# dep-switches.net
KiCad netlist of a schematic drawn in Altium Designer
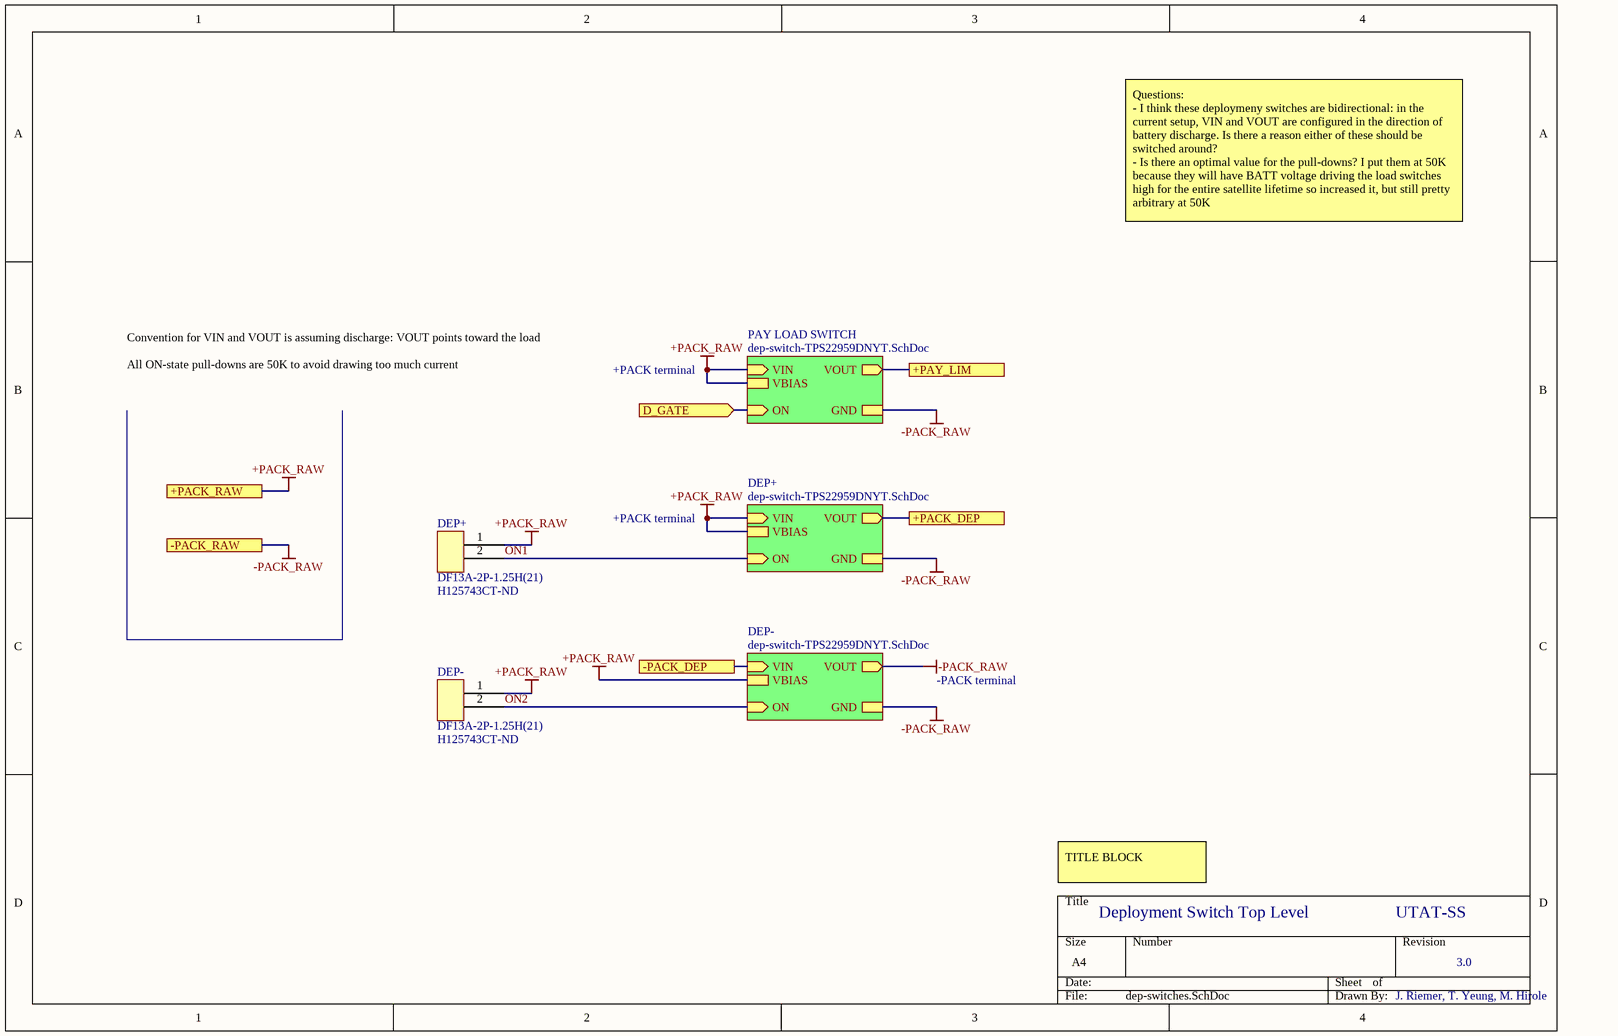
[diagram p0: dep-switches.SchDoc]

(export (version "E")
  (design (tool "Eeschema 10.0.6"))
  (components
    (comp (ref "DEP+")
      (value "DF13A-2P-1.25H(21)")
      (footprint "DF13A-2P-1.25H(21)")
      (description "2 pos DF13 right angle surface mount connector")
      (fields (field (name "SUPPLIER PART NUMBER 1") "H125743CT-ND"))
      (libsource (lib "heron-general") (part "DF13A-2P-1.25H(21)"))
    )
    (comp (ref "DEP-")
      (value "DF13A-2P-1.25H(21)")
      (footprint "DF13A-2P-1.25H(21)")
      (description "2 pos DF13 right angle surface mount connector")
      (fields (field (name "SUPPLIER PART NUMBER 1") "H125743CT-ND"))
      (libsource (lib "heron-general") (part "DF13A-2P-1.25H(21)"))
    )
  )
  (nets
    (net (code "1") (name "+PACK_RAW") (class "Default")
      (node (ref "DEP+") (pin "1") (pintype "passive"))
      (node (ref "DEP-") (pin "1") (pintype "passive"))
    )
    (net (code "7") (name "/ON1") (class "Default") (node (ref "DEP+") (pin "2") (pintype "passive")))
    (net (code "8") (name "/ON2") (class "Default") (node (ref "DEP-") (pin "2") (pintype "passive")))
  )
)
